# ReceiverR2.net
KiCad netlist of a schematic drawn in EAGLE
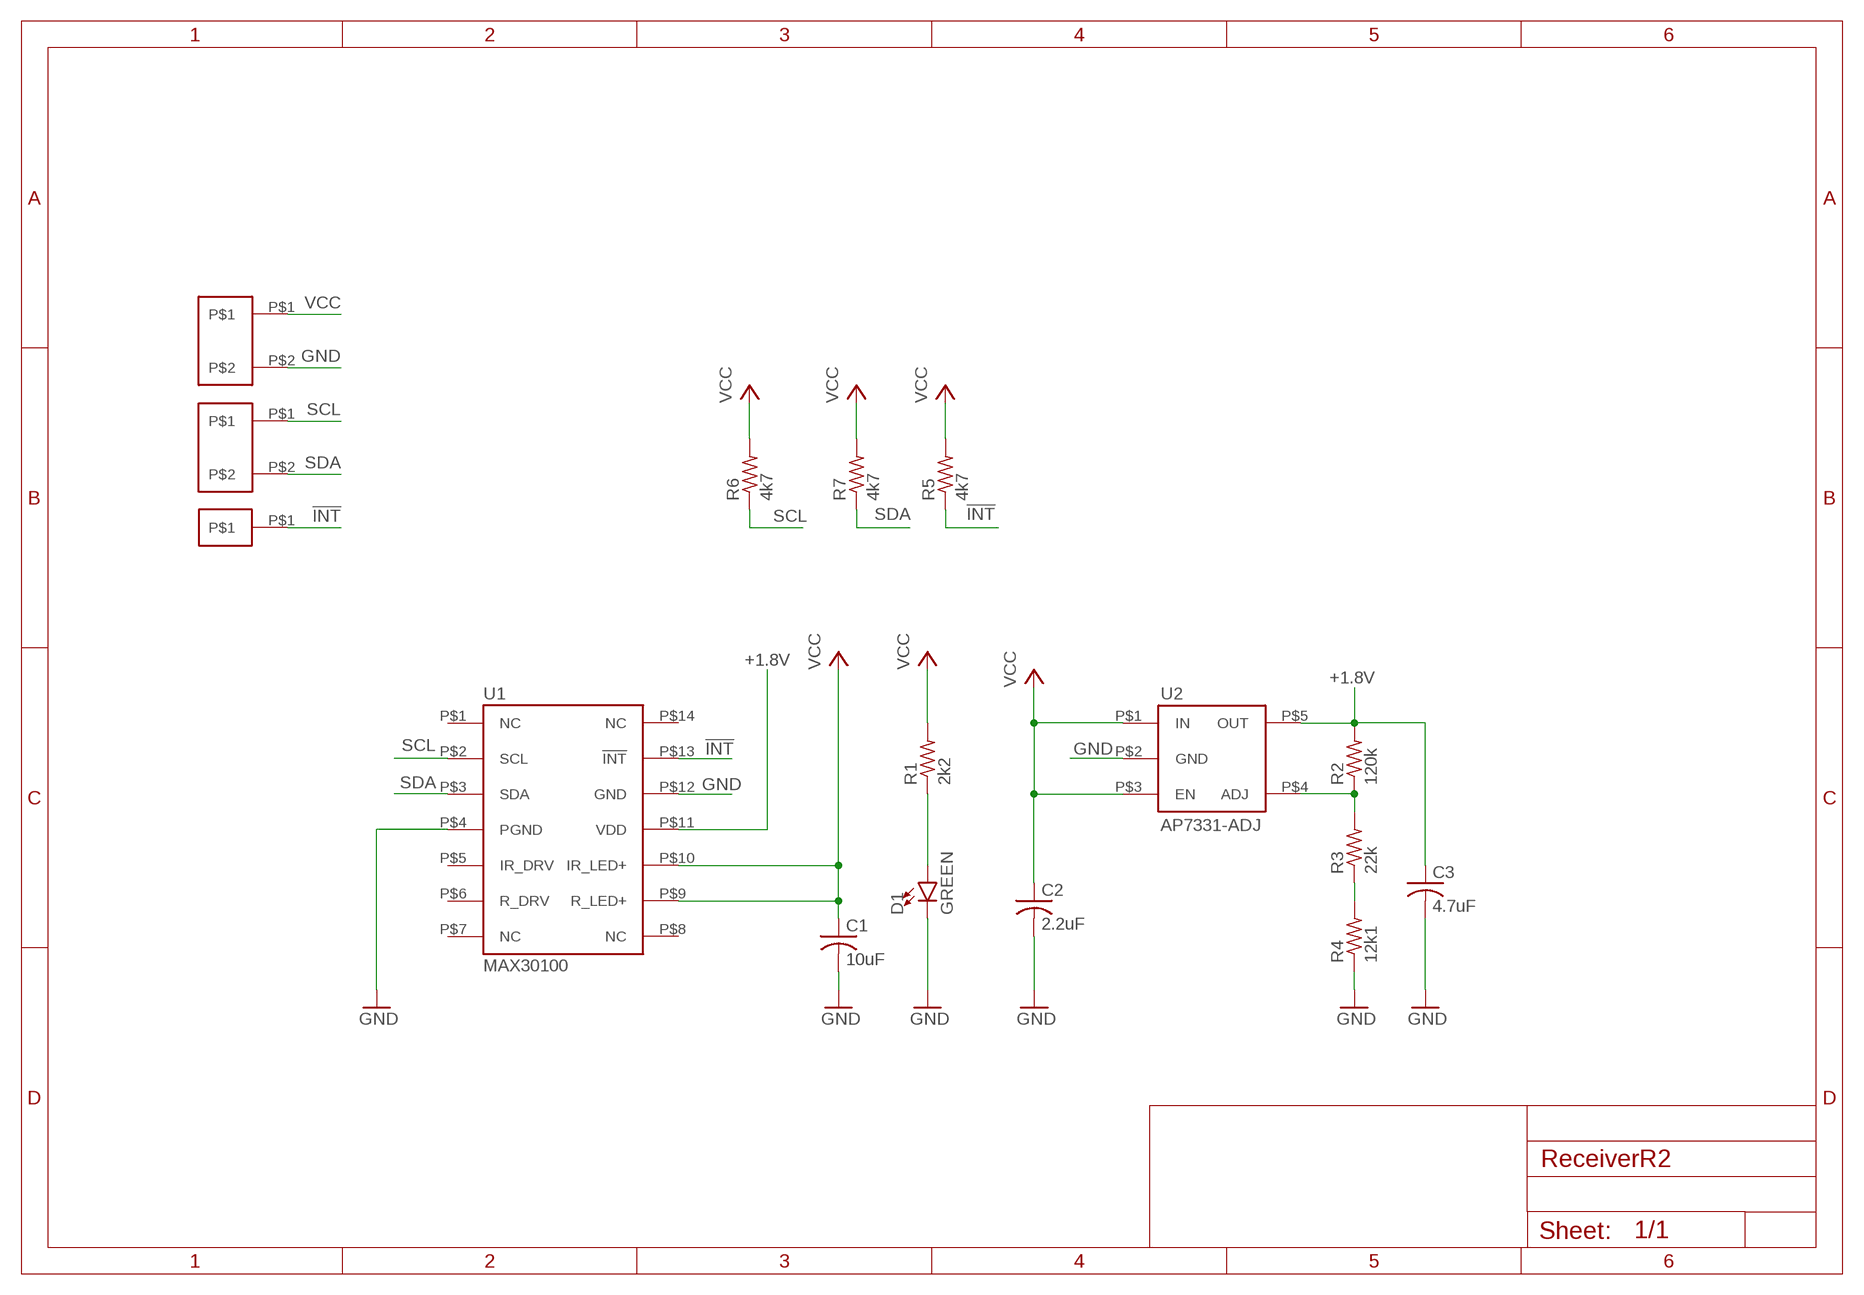
[diagram p0: schematic, sheet 1]

(export (version "E")
  (design (tool "Eeschema 10.0.6"))
  (components
    (comp (ref "C1")
      (value "10uF")
      (footprint "eagle-import:C0805")
      (libsource (lib "eagle-import") (part "C-USC0805"))
    )
    (comp (ref "C2")
      (value "2.2uF")
      (footprint "eagle-import:C0805")
      (libsource (lib "eagle-import") (part "C-USC0805"))
    )
    (comp (ref "C3")
      (value "4.7uF")
      (footprint "eagle-import:C0805")
      (libsource (lib "eagle-import") (part "C-USC0805"))
    )
    (comp (ref "D1")
      (value "GREEN")
      (footprint "eagle-import:LED-0603")
      (libsource (lib "eagle-import") (part "LED-GREEN0603"))
    )
    (comp (ref "J2")
      (value "SOLDERPAD1X2")
      (footprint "eagle-import:SOLDERPAD1X2")
      (libsource (lib "eagle-import") (part "SOLDERPAD1X2"))
    )
    (comp (ref "J3")
      (value "SOLDERPAD1X2")
      (footprint "eagle-import:SOLDERPAD1X2")
      (libsource (lib "eagle-import") (part "SOLDERPAD1X2"))
    )
    (comp (ref "J4")
      (value "SOLDERPAD1X1")
      (footprint "eagle-import:SOLDERPAD1X1")
      (libsource (lib "eagle-import") (part "SOLDERPAD1X1"))
    )
    (comp (ref "R1")
      (value "2k2")
      (footprint "eagle-import:R0805")
      (libsource (lib "eagle-import") (part "R-US_R0805"))
    )
    (comp (ref "R2")
      (value "120k")
      (footprint "eagle-import:R0805")
      (libsource (lib "eagle-import") (part "R-US_R0805"))
    )
    (comp (ref "R3")
      (value "22k")
      (footprint "eagle-import:R0805")
      (libsource (lib "eagle-import") (part "R-US_R0805"))
    )
    (comp (ref "R4")
      (value "12k1")
      (footprint "eagle-import:R0805")
      (libsource (lib "eagle-import") (part "R-US_R0805"))
    )
    (comp (ref "R5")
      (value "4k7")
      (footprint "eagle-import:R0805")
      (libsource (lib "eagle-import") (part "R-US_R0805"))
    )
    (comp (ref "R6")
      (value "4k7")
      (footprint "eagle-import:R0805")
      (libsource (lib "eagle-import") (part "R-US_R0805"))
    )
    (comp (ref "R7")
      (value "4k7")
      (footprint "eagle-import:R0805")
      (libsource (lib "eagle-import") (part "R-US_R0805"))
    )
    (comp (ref "U1")
      (value "MAX30100")
      (footprint "eagle-import:14OESIP")
      (libsource (lib "eagle-import") (part "MAX30100"))
    )
    (comp (ref "U2")
      (value "AP7331-ADJ")
      (footprint "eagle-import:SOT25")
      (libsource (lib "eagle-import") (part "AP7331-ADJ"))
    )
  )
  (nets
    (net (code "1") (name "/+1.8V") (class "Default")
      (node (ref "C3") (pin "1") (pinfunction "1_1") (pintype "passive"))
      (node (ref "R2") (pin "2") (pinfunction "2_2") (pintype "passive"))
      (node (ref "U1") (pin "P$11") (pinfunction "VDD_P$11") (pintype "bidirectional"))
      (node (ref "U2") (pin "P$5") (pinfunction "OUT_P$5") (pintype "bidirectional"))
    )
    (net (code "2") (name "/SCL") (class "Default")
      (node (ref "J3") (pin "P$1") (pinfunction "P$1_P$1") (pintype "bidirectional"))
      (node (ref "R6") (pin "1") (pinfunction "1_1") (pintype "passive"))
      (node (ref "U1") (pin "P$2") (pinfunction "SCL_P$2") (pintype "bidirectional"))
    )
    (net (code "3") (name "/SDA") (class "Default")
      (node (ref "J3") (pin "P$2") (pinfunction "P$2_P$2") (pintype "bidirectional"))
      (node (ref "R7") (pin "1") (pinfunction "1_1") (pintype "passive"))
      (node (ref "U1") (pin "P$3") (pinfunction "SDA_P$3") (pintype "bidirectional"))
    )
    (net (code "4") (name "/~{INT}") (class "Default")
      (node (ref "J4") (pin "P$1") (pinfunction "P$1_P$1") (pintype "bidirectional"))
      (node (ref "R5") (pin "1") (pinfunction "1_1") (pintype "passive"))
      (node (ref "U1") (pin "P$13") (pinfunction "~{INT}_P$13") (pintype "bidirectional"))
    )
    (net (code "5") (name "GND") (class "Default")
      (node (ref "C1") (pin "2") (pinfunction "2_2") (pintype "passive"))
      (node (ref "C2") (pin "2") (pinfunction "2_2") (pintype "passive"))
      (node (ref "C3") (pin "2") (pinfunction "2_2") (pintype "passive"))
      (node (ref "D1") (pin "C") (pinfunction "C_C") (pintype "passive"))
      (node (ref "J2") (pin "P$2") (pinfunction "P$2_P$2") (pintype "bidirectional"))
      (node (ref "R4") (pin "1") (pinfunction "1_1") (pintype "passive"))
      (node (ref "U1") (pin "P$12") (pinfunction "GND_P$12") (pintype "bidirectional"))
      (node (ref "U1") (pin "P$4") (pinfunction "PGND_P$4") (pintype "bidirectional"))
      (node (ref "U2") (pin "P$2") (pinfunction "GND_P$2") (pintype "bidirectional"))
    )
    (net (code "6") (name "Net-(D1-PadA)") (class "Default")
      (node (ref "D1") (pin "A") (pinfunction "A_A") (pintype "passive"))
      (node (ref "R1") (pin "1") (pinfunction "1_1") (pintype "passive"))
    )
    (net (code "7") (name "Net-(R3-Pad1)") (class "Default")
      (node (ref "R3") (pin "1") (pinfunction "1_1") (pintype "passive"))
      (node (ref "R4") (pin "2") (pinfunction "2_2") (pintype "passive"))
    )
    (net (code "8") (name "Net-(U2-ADJ)") (class "Default")
      (node (ref "R2") (pin "1") (pinfunction "1_1") (pintype "passive"))
      (node (ref "R3") (pin "2") (pinfunction "2_2") (pintype "passive"))
      (node (ref "U2") (pin "P$4") (pinfunction "ADJ_P$4") (pintype "bidirectional"))
    )
    (net (code "9") (name "VCC") (class "Default")
      (node (ref "C1") (pin "1") (pinfunction "1_1") (pintype "passive"))
      (node (ref "C2") (pin "1") (pinfunction "1_1") (pintype "passive"))
      (node (ref "J2") (pin "P$1") (pinfunction "P$1_P$1") (pintype "bidirectional"))
      (node (ref "R1") (pin "2") (pinfunction "2_2") (pintype "passive"))
      (node (ref "R5") (pin "2") (pinfunction "2_2") (pintype "passive"))
      (node (ref "R6") (pin "2") (pinfunction "2_2") (pintype "passive"))
      (node (ref "R7") (pin "2") (pinfunction "2_2") (pintype "passive"))
      (node (ref "U1") (pin "P$10") (pinfunction "IR_LED+_P$10") (pintype "bidirectional"))
      (node (ref "U1") (pin "P$9") (pinfunction "R_LED+_P$9") (pintype "bidirectional"))
      (node (ref "U2") (pin "P$1") (pinfunction "IN_P$1") (pintype "bidirectional"))
      (node (ref "U2") (pin "P$3") (pinfunction "EN_P$3") (pintype "bidirectional"))
    )
    (net (code "10") (name "unconnected-(U1-IR_DRV-PadP$5)") (class "Default")
      (node (ref "U1") (pin "P$5") (pinfunction "IR_DRV_P$5") (pintype "bidirectional"))
    )
    (net (code "11") (name "unconnected-(U1-NC-PadP$1)") (class "Default")
      (node (ref "U1") (pin "P$1") (pinfunction "NC_P$1") (pintype "bidirectional"))
    )
    (net (code "12") (name "unconnected-(U1-NC-PadP$7)") (class "Default")
      (node (ref "U1") (pin "P$7") (pinfunction "NC_P$7") (pintype "bidirectional"))
    )
    (net (code "13") (name "unconnected-(U1-NC-PadP$8)") (class "Default")
      (node (ref "U1") (pin "P$8") (pinfunction "NC_P$8") (pintype "bidirectional"))
    )
    (net (code "14") (name "unconnected-(U1-NC-PadP$14)") (class "Default")
      (node (ref "U1") (pin "P$14") (pinfunction "NC_P$14") (pintype "bidirectional"))
    )
    (net (code "15") (name "unconnected-(U1-R_DRV-PadP$6)") (class "Default")
      (node (ref "U1") (pin "P$6") (pinfunction "R_DRV_P$6") (pintype "bidirectional"))
    )
  )
)
